# MCU152A_XDS110_MCU.net
KiCad netlist of a schematic drawn in Altium Designer
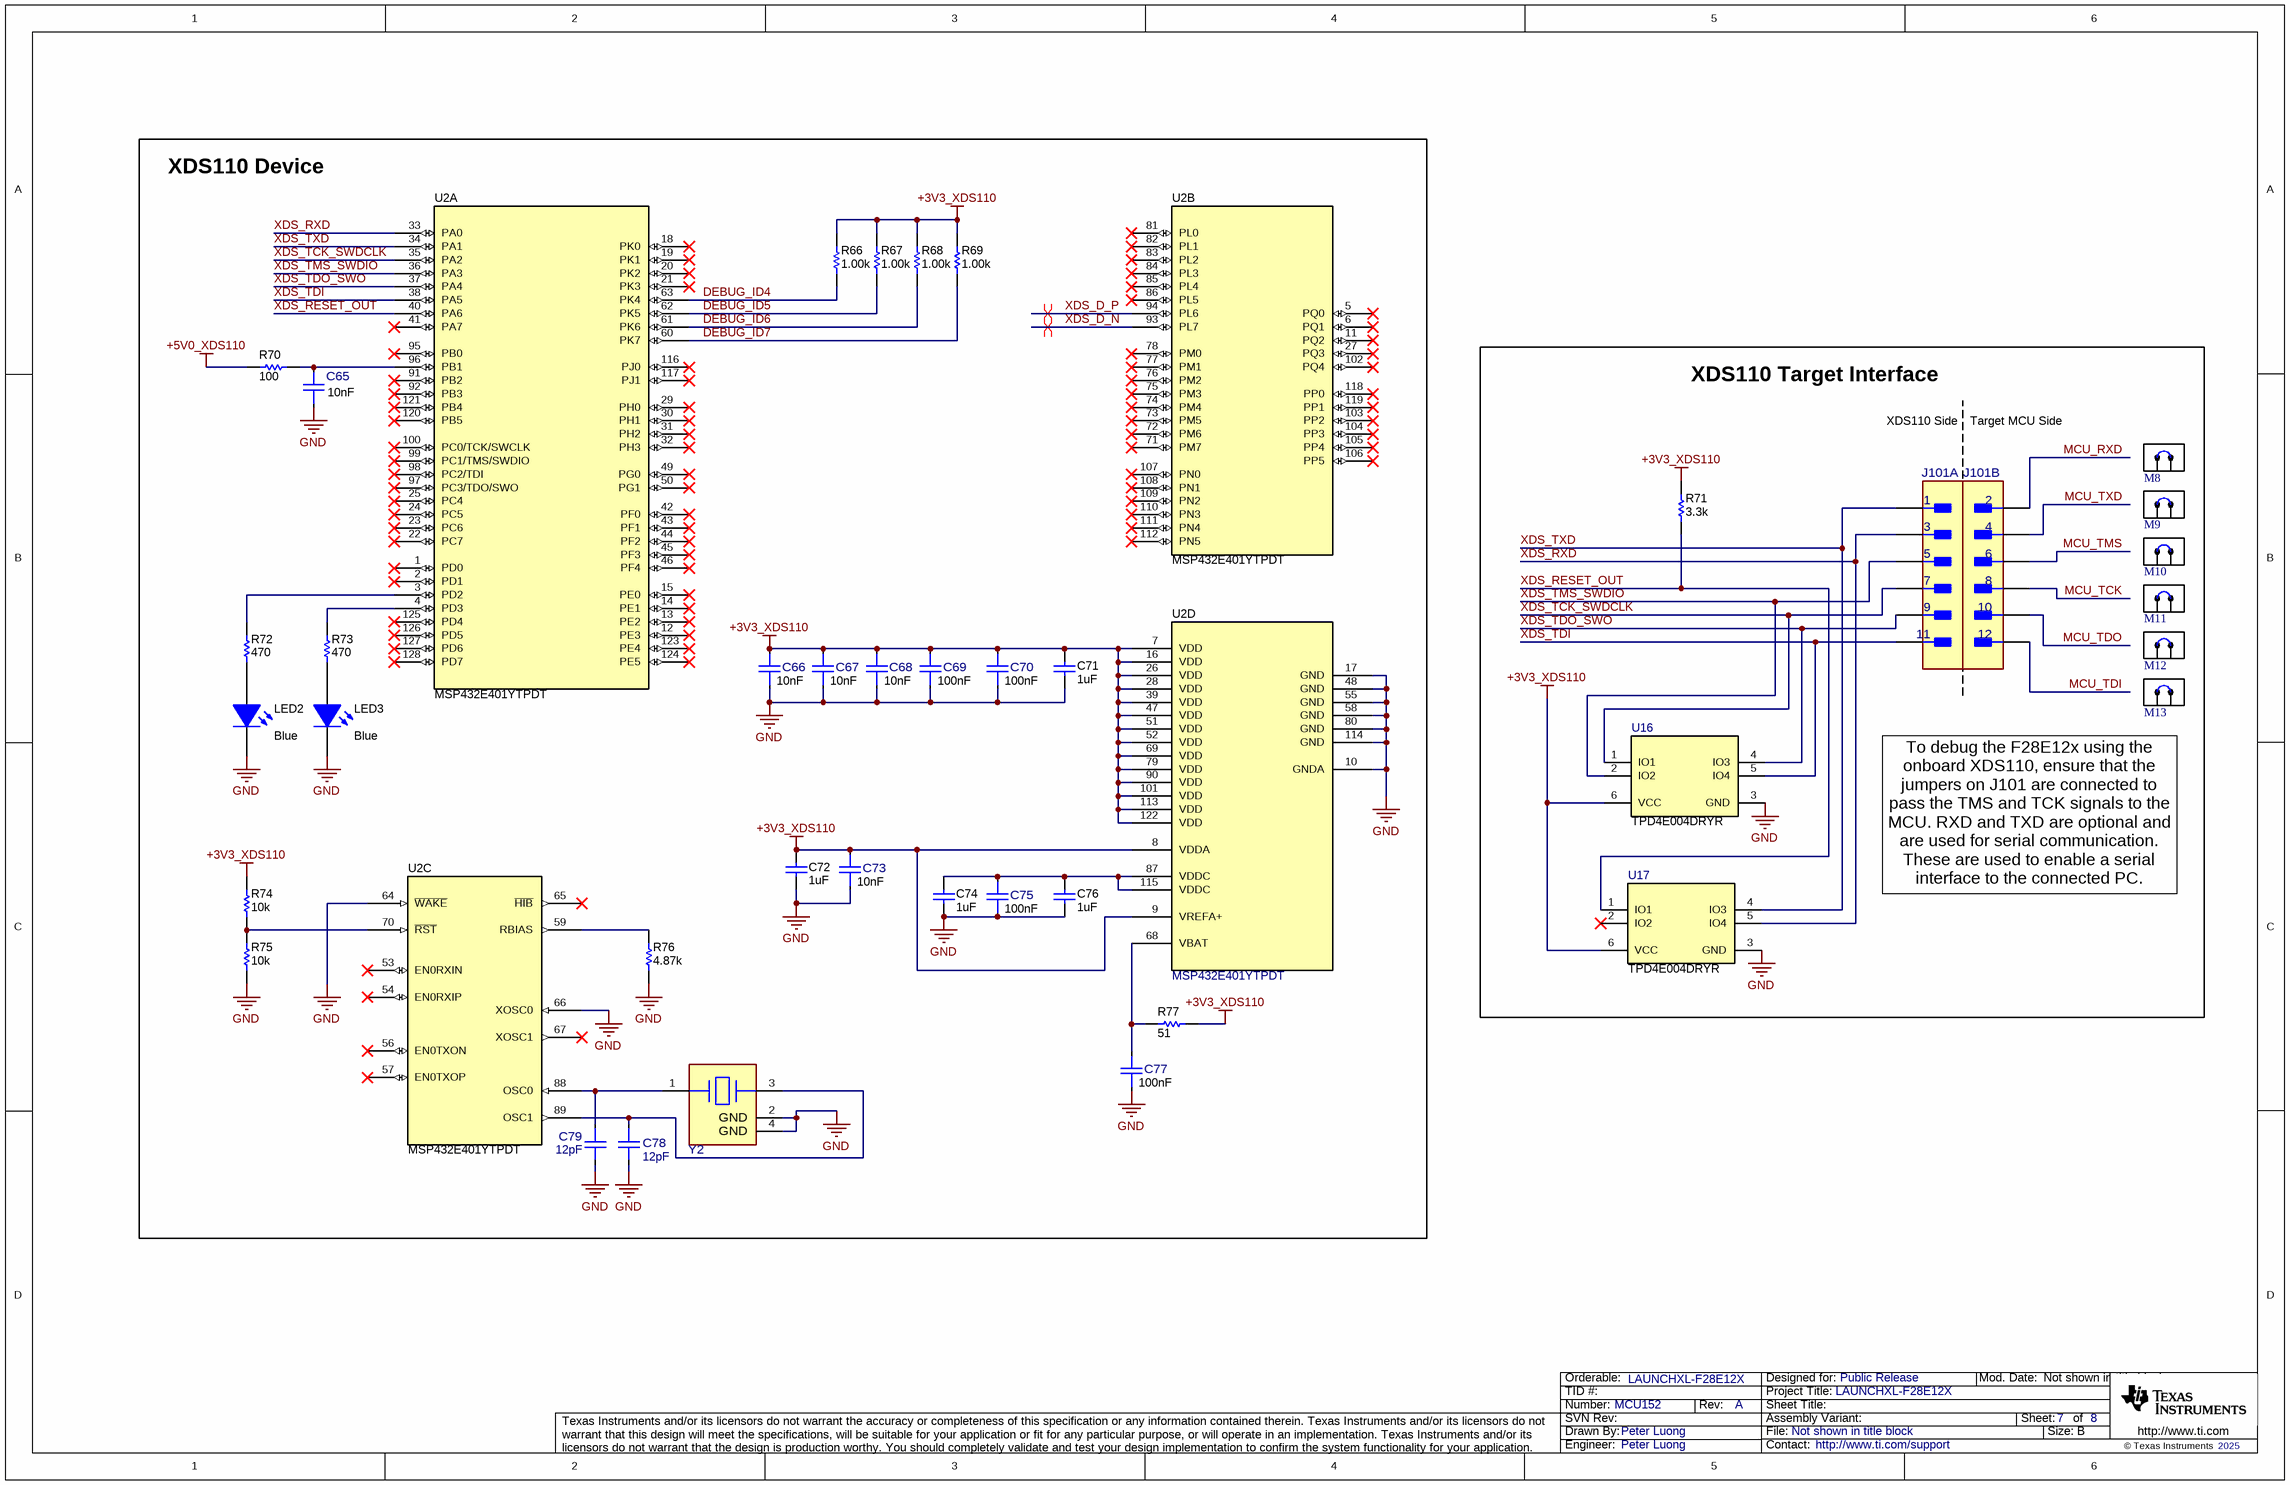
[diagram p0: MCU152A_XDS110_MCU.SchDoc]

(export (version "E")
  (design (tool "Eeschema 10.0.6"))
  (components
    (comp (ref "C65")
      (value "885012205050")
      (footprint "FP-885012205050_0402-MFG")
      (description "10000pF ±10% 25V Ceramic Capacitor X7R 0402 (1005 Metric)")
      (fields
        (field (name "MANUFACTURER") "Wurth Electronics")
        (field (name "CAP_F") "10nF")
        (field (name "MOUSER PART NUMBER") "710-885012205050")
      )
      (libsource (lib "Altium Vault - TI") (part "SYM-885012205050"))
    )
    (comp (ref "C66")
      (value "885012205050")
      (footprint "FP-885012205050_0402-MFG")
      (description "10000pF ±10% 25V Ceramic Capacitor X7R 0402 (1005 Metric)")
      (fields
        (field (name "MANUFACTURER") "Wurth Electronics")
        (field (name "CAP_F") "10nF")
        (field (name "MOUSER PART NUMBER") "710-885012205050")
      )
      (libsource (lib "Altium Vault - TI") (part "SYM-885012205050"))
    )
    (comp (ref "C67")
      (value "885012205050")
      (footprint "FP-885012205050_0402-MFG")
      (description "10000pF ±10% 25V Ceramic Capacitor X7R 0402 (1005 Metric)")
      (fields
        (field (name "MANUFACTURER") "Wurth Electronics")
        (field (name "CAP_F") "10nF")
        (field (name "MOUSER PART NUMBER") "710-885012205050")
      )
      (libsource (lib "Altium Vault - TI") (part "SYM-885012205050"))
    )
    (comp (ref "C68")
      (value "885012205050")
      (footprint "FP-885012205050_0402-MFG")
      (description "10000pF ±10% 25V Ceramic Capacitor X7R 0402 (1005 Metric)")
      (fields
        (field (name "MANUFACTURER") "Wurth Electronics")
        (field (name "CAP_F") "10nF")
        (field (name "MOUSER PART NUMBER") "710-885012205050")
      )
      (libsource (lib "Altium Vault - TI") (part "SYM-885012205050"))
    )
    (comp (ref "C69")
      (value "885012205018")
      (footprint "FP-885012205018_0402-MFG")
      (description "0.1µF ±10% 10V Ceramic Capacitor X7R 0402 (1005 Metric)")
      (fields
        (field (name "MANUFACTURER") "Wurth Electronics")
        (field (name "MOUSER PART NUMBER") "710-885012205018")
        (field (name "CAP_F") "100nF")
      )
      (libsource (lib "Altium Vault - TI") (part "SYM-885012205018"))
    )
    (comp (ref "C70")
      (value "885012205018")
      (footprint "FP-885012205018_0402-MFG")
      (description "0.1µF ±10% 10V Ceramic Capacitor X7R 0402 (1005 Metric)")
      (fields
        (field (name "MANUFACTURER") "Wurth Electronics")
        (field (name "MOUSER PART NUMBER") "710-885012205018")
        (field (name "CAP_F") "100nF")
      )
      (libsource (lib "Altium Vault - TI") (part "SYM-885012205018"))
    )
    (comp (ref "C71")
      (value "885012105012")
      (footprint "0402")
      (description "CAP, CERM, 1 uF, 10 V,+/- 20%, X5R, 0402")
      (fields
        (field (name "VALUEDISPLAYED") "1uF")
        (field (name "MANUFACTURER") "Wurth Elektronik")
        (field (name "PUBLISHER") "Texas Instruments")
      )
      (libsource (lib "Altium Vault - TI") (part "Capacitor"))
    )
    (comp (ref "C72")
      (value "885012105012")
      (footprint "0402")
      (description "CAP, CERM, 1 uF, 10 V,+/- 20%, X5R, 0402")
      (fields
        (field (name "VALUEDISPLAYED") "1uF")
        (field (name "MANUFACTURER") "Wurth Elektronik")
        (field (name "PUBLISHER") "Texas Instruments")
      )
      (libsource (lib "Altium Vault - TI") (part "Capacitor"))
    )
    (comp (ref "C73")
      (value "885012205050")
      (footprint "FP-885012205050_0402-MFG")
      (description "10000pF ±10% 25V Ceramic Capacitor X7R 0402 (1005 Metric)")
      (fields
        (field (name "MANUFACTURER") "Wurth Electronics")
        (field (name "CAP_F") "10nF")
        (field (name "MOUSER PART NUMBER") "710-885012205050")
      )
      (libsource (lib "Altium Vault - TI") (part "SYM-885012205050"))
    )
    (comp (ref "C74")
      (value "885012105012")
      (footprint "0402")
      (description "CAP, CERM, 1 uF, 10 V,+/- 20%, X5R, 0402")
      (fields
        (field (name "VALUEDISPLAYED") "1uF")
        (field (name "MANUFACTURER") "Wurth Elektronik")
        (field (name "PUBLISHER") "Texas Instruments")
      )
      (libsource (lib "Altium Vault - TI") (part "Capacitor"))
    )
    (comp (ref "C75")
      (value "885012205018")
      (footprint "FP-885012205018_0402-MFG")
      (description "0.1µF ±10% 10V Ceramic Capacitor X7R 0402 (1005 Metric)")
      (fields
        (field (name "MANUFACTURER") "Wurth Electronics")
        (field (name "MOUSER PART NUMBER") "710-885012205018")
        (field (name "CAP_F") "100nF")
      )
      (libsource (lib "Altium Vault - TI") (part "SYM-885012205018"))
    )
    (comp (ref "C76")
      (value "885012105012")
      (footprint "0402")
      (description "CAP, CERM, 1 uF, 10 V,+/- 20%, X5R, 0402")
      (fields
        (field (name "VALUEDISPLAYED") "1uF")
        (field (name "MANUFACTURER") "Wurth Elektronik")
        (field (name "PUBLISHER") "Texas Instruments")
      )
      (libsource (lib "Altium Vault - TI") (part "Capacitor"))
    )
    (comp (ref "C77")
      (value "885012205018")
      (footprint "FP-885012205018_0402-MFG")
      (description "0.1µF ±10% 10V Ceramic Capacitor X7R 0402 (1005 Metric)")
      (fields
        (field (name "MANUFACTURER") "Wurth Electronics")
        (field (name "MOUSER PART NUMBER") "710-885012205018")
        (field (name "CAP_F") "100nF")
      )
      (libsource (lib "Altium Vault - TI") (part "SYM-885012205018"))
    )
    (comp (ref "C78")
      (value "885392005127")
      (footprint "FP-885392005127_0402-MFG")
      (description "12 pF ±2% 50V Ceramic Capacitor C0G, NP0 0402 (1005 Metric)")
      (fields
        (field (name "MANUFACTURER") "Wurth")
        (field (name "VALUEDISPLAYED") "12pF")
        (field (name "DIGIKEY PART NUMBER") "732-885392005127CT-ND")
      )
      (libsource (lib "Altium Vault - TI") (part "SYM-885392005127"))
    )
    (comp (ref "C79")
      (value "885392005127")
      (footprint "FP-885392005127_0402-MFG")
      (description "12 pF ±2% 50V Ceramic Capacitor C0G, NP0 0402 (1005 Metric)")
      (fields
        (field (name "MANUFACTURER") "Wurth")
        (field (name "VALUEDISPLAYED") "12pF")
        (field (name "DIGIKEY PART NUMBER") "732-885392005127CT-ND")
      )
      (libsource (lib "Altium Vault - TI") (part "SYM-885392005127"))
    )
    (comp (ref "J101")
      (value "61301221121")
      (footprint "FP-61301221121_HDR12-MFG")
      (description "THT Vertical Pin Header WR-PHD, Pitch 2.54 mm, Dual Row, 12 pins")
      (fields
        (field (name "MOUSER PART NUMBER") "710-61301221121")
        (field (name "MANUFACTURER") "Wurth Electronics")
      )
      (libsource (lib "Altium Vault - TI") (part "SYM-61301221121"))
    )
    (comp (ref "LED2")
      (value "Blue")
      (footprint "WL-SMCW_Blue_0805")
      (description "LED, Blue, SMD")
      (fields (field (name "MANUFACTURER") "Wurth Elektronik") (field (name "PARTNUMBER") "150080BS75000"))
      (libsource (lib "Altium Vault - TI") (part "LED_A2_K1"))
    )
    (comp (ref "LED3")
      (value "Blue")
      (footprint "WL-SMCW_Blue_0805")
      (description "LED, Blue, SMD")
      (fields (field (name "MANUFACTURER") "Wurth Elektronik") (field (name "PARTNUMBER") "150080BS75000"))
      (libsource (lib "Altium Vault - TI") (part "LED_A2_K1"))
    )
    (comp (ref "M8")
      (value "60900213421")
      (footprint "Wurth_60900213421")
      (description "Shunt, 2.54mm, Gold, Black")
      (fields (field (name "MANUFACTURER") "Wurth Elektronik"))
      (libsource (lib "Altium Vault - TI") (part "Shunt"))
    )
    (comp (ref "M9")
      (value "60900213421")
      (footprint "Wurth_60900213421")
      (description "Shunt, 2.54mm, Gold, Black")
      (fields (field (name "MANUFACTURER") "Wurth Elektronik"))
      (libsource (lib "Altium Vault - TI") (part "Shunt"))
    )
    (comp (ref "M10")
      (value "60900213421")
      (footprint "Wurth_60900213421")
      (description "Shunt, 2.54mm, Gold, Black")
      (fields (field (name "MANUFACTURER") "Wurth Elektronik"))
      (libsource (lib "Altium Vault - TI") (part "Shunt"))
    )
    (comp (ref "M11")
      (value "60900213421")
      (footprint "Wurth_60900213421")
      (description "Shunt, 2.54mm, Gold, Black")
      (fields (field (name "MANUFACTURER") "Wurth Elektronik"))
      (libsource (lib "Altium Vault - TI") (part "Shunt"))
    )
    (comp (ref "M12")
      (value "60900213421")
      (footprint "Wurth_60900213421")
      (description "Shunt, 2.54mm, Gold, Black")
      (fields (field (name "MANUFACTURER") "Wurth Elektronik"))
      (libsource (lib "Altium Vault - TI") (part "Shunt"))
    )
    (comp (ref "M13")
      (value "60900213421")
      (footprint "Wurth_60900213421")
      (description "Shunt, 2.54mm, Gold, Black")
      (fields (field (name "MANUFACTURER") "Wurth Elektronik"))
      (libsource (lib "Altium Vault - TI") (part "Shunt"))
    )
    (comp (ref "R66")
      (value "CRCW04021K00FKED")
      (footprint "0402")
      (description "RES, 1.00 k, 1%, 0.063 W, AEC-Q200 Grade 0, 0402")
      (fields (field (name "MANUFACTURER") "Vishay-Dale") (field (name "VALUEDISPLAYED") "1.00k"))
      (libsource (lib "Altium Vault - TI") (part "Resistor"))
    )
    (comp (ref "R67")
      (value "CRCW04021K00FKED")
      (footprint "0402")
      (description "RES, 1.00 k, 1%, 0.063 W, AEC-Q200 Grade 0, 0402")
      (fields (field (name "MANUFACTURER") "Vishay-Dale") (field (name "VALUEDISPLAYED") "1.00k"))
      (libsource (lib "Altium Vault - TI") (part "Resistor"))
    )
    (comp (ref "R68")
      (value "CRCW04021K00FKED")
      (footprint "0402")
      (description "RES, 1.00 k, 1%, 0.063 W, AEC-Q200 Grade 0, 0402")
      (fields (field (name "MANUFACTURER") "Vishay-Dale") (field (name "VALUEDISPLAYED") "1.00k"))
      (libsource (lib "Altium Vault - TI") (part "Resistor"))
    )
    (comp (ref "R69")
      (value "CRCW04021K00FKED")
      (footprint "0402")
      (description "RES, 1.00 k, 1%, 0.063 W, AEC-Q200 Grade 0, 0402")
      (fields (field (name "MANUFACTURER") "Vishay-Dale") (field (name "VALUEDISPLAYED") "1.00k"))
      (libsource (lib "Altium Vault - TI") (part "Resistor"))
    )
    (comp (ref "R70")
      (value "CRCW0402100RJNED")
      (footprint "0402")
      (description "RES, 100, 5%, 0.063 W, AEC-Q200 Grade 0, 0402")
      (fields (field (name "VALUEDISPLAYED") "100") (field (name "MANUFACTURER") "Vishay-Dale"))
      (libsource (lib "Altium Vault - TI") (part "Resistor"))
    )
    (comp (ref "R71")
      (value "CRCW04023K30JNED")
      (footprint "0402")
      (description "RES, 3.3 k, 5%, 0.063 W, AEC-Q200 Grade 0, 0402")
      (fields (field (name "VALUEDISPLAYED") "3.3k") (field (name "MANUFACTURER") "Vishay-Dale"))
      (libsource (lib "Altium Vault - TI") (part "Resistor"))
    )
    (comp (ref "R72")
      (value "RC0402FR-07470RL")
      (footprint "0402")
      (description "RES, 470, 1%, 0.063 W, 0402")
      (fields
        (field (name "MANUFACTURER") "Yageo America")
        (field (name "VALUEDISPLAYED") "470")
        (field (name "PUBLISHER") "Texas Instruments")
      )
      (libsource (lib "Altium Vault - TI") (part "Resistor"))
    )
    (comp (ref "R73")
      (value "RC0402FR-07470RL")
      (footprint "0402")
      (description "RES, 470, 1%, 0.063 W, 0402")
      (fields
        (field (name "MANUFACTURER") "Yageo America")
        (field (name "VALUEDISPLAYED") "470")
        (field (name "PUBLISHER") "Texas Instruments")
      )
      (libsource (lib "Altium Vault - TI") (part "Resistor"))
    )
    (comp (ref "R74")
      (value "CRCW040210K0JNED")
      (footprint "0402")
      (description "RES, 10 k, 5%, 0.063 W, AEC-Q200 Grade 0, 0402")
      (fields (field (name "VALUEDISPLAYED") "10k") (field (name "MANUFACTURER") "Vishay-Dale"))
      (libsource (lib "Altium Vault - TI") (part "Resistor"))
    )
    (comp (ref "R75")
      (value "CRCW040210K0JNED")
      (footprint "0402")
      (description "RES, 10 k, 5%, 0.063 W, AEC-Q200 Grade 0, 0402")
      (fields (field (name "VALUEDISPLAYED") "10k") (field (name "MANUFACTURER") "Vishay-Dale"))
      (libsource (lib "Altium Vault - TI") (part "Resistor"))
    )
    (comp (ref "R76")
      (value "CRCW04024K87FKED")
      (footprint "0402")
      (description "RES, 4.87 k, 1%, 0.063 W, AEC-Q200 Grade 0, 0402")
      (fields (field (name "VALUEDISPLAYED") "4.87k") (field (name "MANUFACTURER") "Vishay-Dale"))
      (libsource (lib "Altium Vault - TI") (part "Resistor"))
    )
    (comp (ref "R77")
      (value "CRCW040251R0JNED")
      (footprint "0402")
      (description "RES, 51, 5%, 0.063 W, AEC-Q200 Grade 0, 0402")
      (fields (field (name "VALUEDISPLAYED") "51") (field (name "MANUFACTURER") "Vishay-Dale"))
      (libsource (lib "Altium Vault - TI") (part "Resistor"))
    )
    (comp (ref "U2")
      (value "MSP432E401YTPDT")
      (footprint "PDT0128A")
      (description "MSP432E401YTPDT, PDT0128A (TQFP-128)")
      (fields
        (field (name "ALTERNATE PARTNUMBER") "MSP432E401YTPDTR")
        (field (name "MANUFACTURER") "Texas Instruments")
        (field (name "PARTNUMBER") "MSP432E401YTPDT")
      )
      (libsource (lib "Altium Vault - TI") (part "MSP432E401YTPDT"))
    )
    (comp (ref "U16")
      (value "TPD4E004DRYR")
      (footprint "DRY0006A")
      (description "4-Channel ESD Protection Array for High-Speed Data Interfaces, DRY0006A (USON-6)")
      (fields (field (name "MANUFACTURER") "Texas Instruments") (field (name "PARTNUMBER") "TPD4E004DRYR"))
      (libsource (lib "Altium Vault - TI") (part "TI-TPD4E004-SON_DRY-6"))
    )
    (comp (ref "U17")
      (value "TPD4E004DRYR")
      (footprint "DRY0006A")
      (description "4-Channel ESD Protection Array for High-Speed Data Interfaces, DRY0006A (USON-6)")
      (fields (field (name "MANUFACTURER") "Texas Instruments") (field (name "PARTNUMBER") "TPD4E004DRYR"))
      (libsource (lib "Altium Vault - TI") (part "TI-TPD4E004-SON_DRY-6"))
    )
    (comp (ref "Y2")
      (value "830064296")
      (footprint "FP-830064296_SMT4_3MM4_2MM7-MFG")
      (description "Crystal 16 MHz ±20ppm Crystal 8pF 70 Ohms 4-SMD, No Lead")
      (fields
        (field (name "MOUSER PART NUMBER") "710-830064296")
        (field (name "DIGIKEY PART NUMBER") "732-830064296CT-ND")
      )
      (libsource (lib "Altium Vault - TI") (part "SYM-830064296"))
    )
  )
  (nets
    (net (code "1") (name "+3V3_XDS110") (class "Default")
      (node (ref "C66") (pin "2") (pinfunction "2_2") (pintype "passive"))
      (node (ref "C67") (pin "2") (pinfunction "2_2") (pintype "passive"))
      (node (ref "C68") (pin "2") (pinfunction "2_2") (pintype "passive"))
      (node (ref "C69") (pin "2") (pinfunction "2_2") (pintype "passive"))
      (node (ref "C70") (pin "2") (pinfunction "2_2") (pintype "passive"))
      (node (ref "C71") (pin "1") (pinfunction "1_1") (pintype "passive"))
      (node (ref "C72") (pin "1") (pinfunction "1_1") (pintype "passive"))
      (node (ref "C73") (pin "2") (pinfunction "2_2") (pintype "passive"))
      (node (ref "R66") (pin "2") (pinfunction "2_2") (pintype "passive"))
      (node (ref "R67") (pin "2") (pinfunction "2_2") (pintype "passive"))
      (node (ref "R68") (pin "2") (pinfunction "2_2") (pintype "passive"))
      (node (ref "R69") (pin "2") (pinfunction "2_2") (pintype "passive"))
      (node (ref "R71") (pin "2") (pinfunction "2_2") (pintype "passive"))
      (node (ref "R74") (pin "2") (pinfunction "2_2") (pintype "passive"))
      (node (ref "R77") (pin "2") (pinfunction "2_2") (pintype "passive"))
      (node (ref "U16") (pin "6") (pinfunction "VCC_6") (pintype "power_in"))
      (node (ref "U17") (pin "6") (pinfunction "VCC_6") (pintype "power_in"))
      (node (ref "U2") (pin "101") (pinfunction "VDD_101") (pintype "power_in"))
      (node (ref "U2") (pin "113") (pinfunction "VDD_113") (pintype "power_in"))
      (node (ref "U2") (pin "122") (pinfunction "VDD_122") (pintype "power_in"))
      (node (ref "U2") (pin "16") (pinfunction "VDD_16") (pintype "power_in"))
      (node (ref "U2") (pin "26") (pinfunction "VDD_26") (pintype "power_in"))
      (node (ref "U2") (pin "28") (pinfunction "VDD_28") (pintype "power_in"))
      (node (ref "U2") (pin "39") (pinfunction "VDD_39") (pintype "power_in"))
      (node (ref "U2") (pin "47") (pinfunction "VDD_47") (pintype "power_in"))
      (node (ref "U2") (pin "51") (pinfunction "VDD_51") (pintype "power_in"))
      (node (ref "U2") (pin "52") (pinfunction "VDD_52") (pintype "power_in"))
      (node (ref "U2") (pin "69") (pinfunction "VDD_69") (pintype "power_in"))
      (node (ref "U2") (pin "7") (pinfunction "VDD_7") (pintype "power_in"))
      (node (ref "U2") (pin "79") (pinfunction "VDD_79") (pintype "power_in"))
      (node (ref "U2") (pin "8") (pinfunction "VDDA_8") (pintype "power_in"))
      (node (ref "U2") (pin "9") (pinfunction "VREFA+_9") (pintype "power_in"))
      (node (ref "U2") (pin "90") (pinfunction "VDD_90") (pintype "power_in"))
    )
    (net (code "2") (name "+5V0_XDS110") (class "Default")
      (node (ref "R70") (pin "1") (pinfunction "1_1") (pintype "passive"))
    )
    (net (code "3") (name "/DEBUG_ID4") (class "Default")
      (node (ref "R66") (pin "1") (pinfunction "1_1") (pintype "passive"))
      (node (ref "U2") (pin "63") (pinfunction "PK4_63") (pintype "bidirectional"))
    )
    (net (code "4") (name "/DEBUG_ID5") (class "Default")
      (node (ref "R67") (pin "1") (pinfunction "1_1") (pintype "passive"))
      (node (ref "U2") (pin "62") (pinfunction "PK5_62") (pintype "bidirectional"))
    )
    (net (code "5") (name "/DEBUG_ID6") (class "Default")
      (node (ref "R68") (pin "1") (pinfunction "1_1") (pintype "passive"))
      (node (ref "U2") (pin "61") (pinfunction "PK6_61") (pintype "bidirectional"))
    )
    (net (code "6") (name "/DEBUG_ID7") (class "Default")
      (node (ref "R69") (pin "1") (pinfunction "1_1") (pintype "passive"))
      (node (ref "U2") (pin "60") (pinfunction "PK7_60") (pintype "bidirectional"))
    )
    (net (code "7") (name "/MCU_RXD") (class "Default")
      (node (ref "J101") (pin "2") (pinfunction "2_2") (pintype "passive"))
    )
    (net (code "8") (name "/MCU_TCK") (class "Default")
      (node (ref "J101") (pin "8") (pinfunction "8_8") (pintype "passive"))
    )
    (net (code "9") (name "/MCU_TDI") (class "Default")
      (node (ref "J101") (pin "12") (pinfunction "12_12") (pintype "passive"))
    )
    (net (code "10") (name "/MCU_TDO") (class "Default")
      (node (ref "J101") (pin "10") (pinfunction "10_10") (pintype "passive"))
    )
    (net (code "11") (name "/MCU_TMS") (class "Default")
      (node (ref "J101") (pin "6") (pinfunction "6_6") (pintype "passive"))
    )
    (net (code "12") (name "/MCU_TXD") (class "Default")
      (node (ref "J101") (pin "4") (pinfunction "4_4") (pintype "passive"))
    )
    (net (code "13") (name "/XDS_D_N") (class "Default")
      (node (ref "U2") (pin "93") (pinfunction "PL7_93") (pintype "bidirectional"))
    )
    (net (code "14") (name "/XDS_D_P") (class "Default")
      (node (ref "U2") (pin "94") (pinfunction "PL6_94") (pintype "bidirectional"))
    )
    (net (code "15") (name "/XDS_RESET_OUT") (class "Default")
      (node (ref "R71") (pin "1") (pinfunction "1_1") (pintype "passive"))
      (node (ref "U17") (pin "1") (pinfunction "IO1_1") (pintype "passive"))
      (node (ref "U2") (pin "40") (pinfunction "PA6_40") (pintype "bidirectional"))
    )
    (net (code "16") (name "/XDS_RXD") (class "Default")
      (node (ref "J101") (pin "3") (pinfunction "3_3") (pintype "passive"))
      (node (ref "U17") (pin "5") (pinfunction "IO4_5") (pintype "passive"))
      (node (ref "U2") (pin "33") (pinfunction "PA0_33") (pintype "bidirectional"))
    )
    (net (code "17") (name "/XDS_TCK_SWDCLK") (class "Default")
      (node (ref "J101") (pin "7") (pinfunction "7_7") (pintype "passive"))
      (node (ref "U16") (pin "1") (pinfunction "IO1_1") (pintype "passive"))
      (node (ref "U2") (pin "35") (pinfunction "PA2_35") (pintype "bidirectional"))
    )
    (net (code "18") (name "/XDS_TDI") (class "Default")
      (node (ref "J101") (pin "11") (pinfunction "11_11") (pintype "passive"))
      (node (ref "U16") (pin "5") (pinfunction "IO4_5") (pintype "passive"))
      (node (ref "U2") (pin "38") (pinfunction "PA5_38") (pintype "bidirectional"))
    )
    (net (code "19") (name "/XDS_TDO_SWO") (class "Default")
      (node (ref "J101") (pin "9") (pinfunction "9_9") (pintype "passive"))
      (node (ref "U16") (pin "4") (pinfunction "IO3_4") (pintype "passive"))
      (node (ref "U2") (pin "37") (pinfunction "PA4_37") (pintype "bidirectional"))
    )
    (net (code "20") (name "/XDS_TMS_SWDIO") (class "Default")
      (node (ref "J101") (pin "5") (pinfunction "5_5") (pintype "passive"))
      (node (ref "U16") (pin "2") (pinfunction "IO2_2") (pintype "passive"))
      (node (ref "U2") (pin "36") (pinfunction "PA3_36") (pintype "bidirectional"))
    )
    (net (code "21") (name "/XDS_TXD") (class "Default")
      (node (ref "J101") (pin "1") (pinfunction "1_1") (pintype "passive"))
      (node (ref "U17") (pin "4") (pinfunction "IO3_4") (pintype "passive"))
      (node (ref "U2") (pin "34") (pinfunction "PA1_34") (pintype "bidirectional"))
    )
    (net (code "22") (name "GND") (class "Default")
      (node (ref "C65") (pin "1") (pinfunction "1_1") (pintype "passive"))
      (node (ref "C66") (pin "1") (pinfunction "1_1") (pintype "passive"))
      (node (ref "C67") (pin "1") (pinfunction "1_1") (pintype "passive"))
      (node (ref "C68") (pin "1") (pinfunction "1_1") (pintype "passive"))
      (node (ref "C69") (pin "1") (pinfunction "1_1") (pintype "passive"))
      (node (ref "C70") (pin "1") (pinfunction "1_1") (pintype "passive"))
      (node (ref "C71") (pin "2") (pinfunction "2_2") (pintype "passive"))
      (node (ref "C72") (pin "2") (pinfunction "2_2") (pintype "passive"))
      (node (ref "C73") (pin "1") (pinfunction "1_1") (pintype "passive"))
      (node (ref "C74") (pin "2") (pinfunction "2_2") (pintype "passive"))
      (node (ref "C75") (pin "1") (pinfunction "1_1") (pintype "passive"))
      (node (ref "C76") (pin "2") (pinfunction "2_2") (pintype "passive"))
      (node (ref "C77") (pin "1") (pinfunction "1_1") (pintype "passive"))
      (node (ref "C78") (pin "2") (pinfunction "2_2") (pintype "passive"))
      (node (ref "C79") (pin "2") (pinfunction "2_2") (pintype "passive"))
      (node (ref "LED2") (pin "1") (pinfunction "K_1") (pintype "passive"))
      (node (ref "LED3") (pin "1") (pinfunction "K_1") (pintype "passive"))
      (node (ref "R75") (pin "1") (pinfunction "1_1") (pintype "passive"))
      (node (ref "R76") (pin "1") (pinfunction "1_1") (pintype "passive"))
      (node (ref "U16") (pin "3") (pinfunction "GND_3") (pintype "power_in"))
      (node (ref "U17") (pin "3") (pinfunction "GND_3") (pintype "power_in"))
      (node (ref "U2") (pin "10") (pinfunction "GNDA_10") (pintype "power_in"))
      (node (ref "U2") (pin "114") (pinfunction "GND_114") (pintype "power_in"))
      (node (ref "U2") (pin "17") (pinfunction "GND_17") (pintype "power_in"))
      (node (ref "U2") (pin "48") (pinfunction "GND_48") (pintype "power_in"))
      (node (ref "U2") (pin "55") (pinfunction "GND_55") (pintype "power_in"))
      (node (ref "U2") (pin "58") (pinfunction "GND_58") (pintype "power_in"))
      (node (ref "U2") (pin "64") (pinfunction "WAKE_64") (pintype "input"))
      (node (ref "U2") (pin "66") (pinfunction "XOSC0_66") (pintype "input"))
      (node (ref "U2") (pin "80") (pinfunction "GND_80") (pintype "power_in"))
      (node (ref "Y2") (pin "2") (pinfunction "GND_2") (pintype "power_in"))
      (node (ref "Y2") (pin "4") (pinfunction "GND_4") (pintype "power_in"))
    )
    (net (code "23") (name "Net-(C74-Pad1)") (class "Default")
      (node (ref "C74") (pin "1") (pinfunction "1_1") (pintype "passive"))
      (node (ref "C75") (pin "2") (pinfunction "2_2") (pintype "passive"))
      (node (ref "C76") (pin "1") (pinfunction "1_1") (pintype "passive"))
      (node (ref "U2") (pin "115") (pinfunction "VDDC_115") (pintype "power_in"))
      (node (ref "U2") (pin "87") (pinfunction "VDDC_87") (pintype "power_in"))
    )
    (net (code "24") (name "Net-(LED2-A)") (class "Default")
      (node (ref "LED2") (pin "2") (pinfunction "A_2") (pintype "passive"))
      (node (ref "R72") (pin "1") (pinfunction "1_1") (pintype "passive"))
    )
    (net (code "25") (name "Net-(LED3-A)") (class "Default")
      (node (ref "LED3") (pin "2") (pinfunction "A_2") (pintype "passive"))
      (node (ref "R73") (pin "1") (pinfunction "1_1") (pintype "passive"))
    )
    (net (code "26") (name "Net-(U2A-PB1)") (class "Default")
      (node (ref "C65") (pin "2") (pinfunction "2_2") (pintype "passive"))
      (node (ref "R70") (pin "2") (pinfunction "2_2") (pintype "passive"))
      (node (ref "U2") (pin "96") (pinfunction "PB1_96") (pintype "bidirectional"))
    )
    (net (code "27") (name "Net-(U2A-PD2)") (class "Default")
      (node (ref "R72") (pin "2") (pinfunction "2_2") (pintype "passive"))
      (node (ref "U2") (pin "3") (pinfunction "PD2_3") (pintype "bidirectional"))
    )
    (net (code "28") (name "Net-(U2A-PD3)") (class "Default")
      (node (ref "R73") (pin "2") (pinfunction "2_2") (pintype "passive"))
      (node (ref "U2") (pin "4") (pinfunction "PD3_4") (pintype "bidirectional"))
    )
    (net (code "29") (name "Net-(U2C-OSC0)") (class "Default")
      (node (ref "C79") (pin "1") (pinfunction "1_1") (pintype "passive"))
      (node (ref "U2") (pin "88") (pinfunction "OSC0_88") (pintype "input"))
      (node (ref "Y2") (pin "1") (pinfunction "1_Crystal_1") (pintype "passive"))
    )
    (net (code "30") (name "Net-(U2C-OSC1)") (class "Default")
      (node (ref "C78") (pin "1") (pinfunction "1_1") (pintype "passive"))
      (node (ref "U2") (pin "89") (pinfunction "OSC1_89") (pintype "output"))
      (node (ref "Y2") (pin "3") (pinfunction "2_Crystal_3") (pintype "passive"))
    )
    (net (code "31") (name "Net-(U2C-RBIAS)") (class "Default")
      (node (ref "R76") (pin "2") (pinfunction "2_2") (pintype "passive"))
      (node (ref "U2") (pin "59") (pinfunction "RBIAS_59") (pintype "output"))
    )
    (net (code "32") (name "Net-(U2C-RST)") (class "Default")
      (node (ref "R74") (pin "1") (pinfunction "1_1") (pintype "passive"))
      (node (ref "R75") (pin "2") (pinfunction "2_2") (pintype "passive"))
      (node (ref "U2") (pin "70") (pinfunction "RST_70") (pintype "input"))
    )
    (net (code "33") (name "Net-(U2D-VBAT)") (class "Default")
      (node (ref "C77") (pin "2") (pinfunction "2_2") (pintype "passive"))
      (node (ref "R77") (pin "1") (pinfunction "1_1") (pintype "passive"))
      (node (ref "U2") (pin "68") (pinfunction "VBAT_68") (pintype "power_in"))
    )
    (net (code "34") (name "unconnected-(U2A-PA7-Pad41)") (class "Default")
      (node (ref "U2") (pin "41") (pinfunction "PA7_41") (pintype "bidirectional+no_connect"))
    )
    (net (code "35") (name "unconnected-(U2A-PB0-Pad95)") (class "Default")
      (node (ref "U2") (pin "95") (pinfunction "PB0_95") (pintype "bidirectional+no_connect"))
    )
    (net (code "36") (name "unconnected-(U2A-PB2-Pad91)") (class "Default")
      (node (ref "U2") (pin "91") (pinfunction "PB2_91") (pintype "bidirectional+no_connect"))
    )
    (net (code "37") (name "unconnected-(U2A-PB3-Pad92)") (class "Default")
      (node (ref "U2") (pin "92") (pinfunction "PB3_92") (pintype "bidirectional+no_connect"))
    )
    (net (code "38") (name "unconnected-(U2A-PB4-Pad121)") (class "Default")
      (node (ref "U2") (pin "121") (pinfunction "PB4_121") (pintype "bidirectional+no_connect"))
    )
    (net (code "39") (name "unconnected-(U2A-PB5-Pad120)") (class "Default")
      (node (ref "U2") (pin "120") (pinfunction "PB5_120") (pintype "bidirectional+no_connect"))
    )
    (net (code "40") (name "unconnected-(U2A-PC0{slash}TCK{slash}SWCLK-Pad100)") (class "Default")
      (node (ref "U2") (pin "100") (pinfunction "PC0/TCK/SWCLK_100") (pintype "bidirectional+no_connect"))
    )
    (net (code "41") (name "unconnected-(U2A-PC1{slash}TMS{slash}SWDIO-Pad99)") (class "Default")
      (node (ref "U2") (pin "99") (pinfunction "PC1/TMS/SWDIO_99") (pintype "bidirectional+no_connect"))
    )
    (net (code "42") (name "unconnected-(U2A-PC2{slash}TDI-Pad98)") (class "Default")
      (node (ref "U2") (pin "98") (pinfunction "PC2/TDI_98") (pintype "bidirectional+no_connect"))
    )
    (net (code "43") (name "unconnected-(U2A-PC3{slash}TDO{slash}SWO-Pad97)") (class "Default")
      (node (ref "U2") (pin "97") (pinfunction "PC3/TDO/SWO_97") (pintype "bidirectional+no_connect"))
    )
    (net (code "44") (name "unconnected-(U2A-PC4-Pad25)") (class "Default")
      (node (ref "U2") (pin "25") (pinfunction "PC4_25") (pintype "bidirectional+no_connect"))
    )
    (net (code "45") (name "unconnected-(U2A-PC5-Pad24)") (class "Default")
      (node (ref "U2") (pin "24") (pinfunction "PC5_24") (pintype "bidirectional+no_connect"))
    )
    (net (code "46") (name "unconnected-(U2A-PC6-Pad23)") (class "Default")
      (node (ref "U2") (pin "23") (pinfunction "PC6_23") (pintype "bidirectional+no_connect"))
    )
    (net (code "47") (name "unconnected-(U2A-PC7-Pad22)") (class "Default")
      (node (ref "U2") (pin "22") (pinfunction "PC7_22") (pintype "bidirectional+no_connect"))
    )
    (net (code "48") (name "unconnected-(U2A-PD0-Pad1)") (class "Default")
      (node (ref "U2") (pin "1") (pinfunction "PD0_1") (pintype "bidirectional+no_connect"))
    )
    (net (code "49") (name "unconnected-(U2A-PD1-Pad2)") (class "Default")
      (node (ref "U2") (pin "2") (pinfunction "PD1_2") (pintype "bidirectional+no_connect"))
    )
    (net (code "50") (name "unconnected-(U2A-PD4-Pad125)") (class "Default")
      (node (ref "U2") (pin "125") (pinfunction "PD4_125") (pintype "bidirectional+no_connect"))
    )
    (net (code "51") (name "unconnected-(U2A-PD5-Pad126)") (class "Default")
      (node (ref "U2") (pin "126") (pinfunction "PD5_126") (pintype "bidirectional+no_connect"))
    )
    (net (code "52") (name "unconnected-(U2A-PD6-Pad127)") (class "Default")
      (node (ref "U2") (pin "127") (pinfunction "PD6_127") (pintype "bidirectional+no_connect"))
    )
    (net (code "53") (name "unconnected-(U2A-PD7-Pad128)") (class "Default")
      (node (ref "U2") (pin "128") (pinfunction "PD7_128") (pintype "bidirectional+no_connect"))
    )
    (net (code "54") (name "unconnected-(U2A-PE0-Pad15)") (class "Default")
      (node (ref "U2") (pin "15") (pinfunction "PE0_15") (pintype "bidirectional+no_connect"))
    )
    (net (code "55") (name "unconnected-(U2A-PE1-Pad14)") (class "Default")
      (node (ref "U2") (pin "14") (pinfunction "PE1_14") (pintype "bidirectional+no_connect"))
    )
    (net (code "56") (name "unconnected-(U2A-PE2-Pad13)") (class "Default")
      (node (ref "U2") (pin "13") (pinfunction "PE2_13") (pintype "bidirectional+no_connect"))
    )
    (net (code "57") (name "unconnected-(U2A-PE3-Pad12)") (class "Default")
      (node (ref "U2") (pin "12") (pinfunction "PE3_12") (pintype "bidirectional+no_connect"))
    )
    (net (code "58") (name "unconnected-(U2A-PE4-Pad123)") (class "Default")
      (node (ref "U2") (pin "123") (pinfunction "PE4_123") (pintype "bidirectional+no_connect"))
    )
    (net (code "59") (name "unconnected-(U2A-PE5-Pad124)") (class "Default")
      (node (ref "U2") (pin "124") (pinfunction "PE5_124") (pintype "bidirectional+no_connect"))
    )
    (net (code "60") (name "unconnected-(U2A-PF0-Pad42)") (class "Default")
      (node (ref "U2") (pin "42") (pinfunction "PF0_42") (pintype "bidirectional+no_connect"))
    )
    (net (code "61") (name "unconnected-(U2A-PF1-Pad43)") (class "Default")
      (node (ref "U2") (pin "43") (pinfunction "PF1_43") (pintype "bidirectional+no_connect"))
    )
    (net (code "62") (name "unconnected-(U2A-PF2-Pad44)") (class "Default")
      (node (ref "U2") (pin "44") (pinfunction "PF2_44") (pintype "bidirectional+no_connect"))
    )
    (net (code "63") (name "unconnected-(U2A-PF3-Pad45)") (class "Default")
      (node (ref "U2") (pin "45") (pinfunction "PF3_45") (pintype "bidirectional+no_connect"))
    )
    (net (code "64") (name "unconnected-(U2A-PF4-Pad46)") (class "Default")
      (node (ref "U2") (pin "46") (pinfunction "PF4_46") (pintype "bidirectional+no_connect"))
    )
    (net (code "65") (name "unconnected-(U2A-PG0-Pad49)") (class "Default")
      (node (ref "U2") (pin "49") (pinfunction "PG0_49") (pintype "bidirectional+no_connect"))
    )
    (net (code "66") (name "unconnected-(U2A-PG1-Pad50)") (class "Default")
      (node (ref "U2") (pin "50") (pinfunction "PG1_50") (pintype "bidirectional+no_connect"))
    )
    (net (code "67") (name "unconnected-(U2A-PH0-Pad29)") (class "Default")
      (node (ref "U2") (pin "29") (pinfunction "PH0_29") (pintype "bidirectional+no_connect"))
    )
    (net (code "68") (name "unconnected-(U2A-PH1-Pad30)") (class "Default")
      (node (ref "U2") (pin "30") (pinfunction "PH1_30") (pintype "bidirectional+no_connect"))
    )
    (net (code "69") (name "unconnected-(U2A-PH2-Pad31)") (class "Default")
      (node (ref "U2") (pin "31") (pinfunction "PH2_31") (pintype "bidirectional+no_connect"))
    )
    (net (code "70") (name "unconnected-(U2A-PH3-Pad32)") (class "Default")
      (node (ref "U2") (pin "32") (pinfunction "PH3_32") (pintype "bidirectional+no_connect"))
    )
    (net (code "71") (name "unconnected-(U2A-PJ0-Pad116)") (class "Default")
      (node (ref "U2") (pin "116") (pinfunction "PJ0_116") (pintype "bidirectional+no_connect"))
    )
    (net (code "72") (name "unconnected-(U2A-PJ1-Pad117)") (class "Default")
      (node (ref "U2") (pin "117") (pinfunction "PJ1_117") (pintype "bidirectional+no_connect"))
    )
    (net (code "73") (name "unconnected-(U2A-PK0-Pad18)") (class "Default")
      (node (ref "U2") (pin "18") (pinfunction "PK0_18") (pintype "bidirectional+no_connect"))
    )
    (net (code "74") (name "unconnected-(U2A-PK1-Pad19)") (class "Default")
      (node (ref "U2") (pin "19") (pinfunction "PK1_19") (pintype "bidirectional+no_connect"))
    )
    (net (code "75") (name "unconnected-(U2A-PK2-Pad20)") (class "Default")
      (node (ref "U2") (pin "20") (pinfunction "PK2_20") (pintype "bidirectional+no_connect"))
    )
    (net (code "76") (name "unconnected-(U2A-PK3-Pad21)") (class "Default")
      (node (ref "U2") (pin "21") (pinfunction "PK3_21") (pintype "bidirectional+no_connect"))
    )
    (net (code "77") (name "unconnected-(U2B-PL0-Pad81)") (class "Default")
      (node (ref "U2") (pin "81") (pinfunction "PL0_81") (pintype "bidirectional+no_connect"))
    )
    (net (code "78") (name "unconnected-(U2B-PL1-Pad82)") (class "Default")
      (node (ref "U2") (pin "82") (pinfunction "PL1_82") (pintype "bidirectional+no_connect"))
    )
    (net (code "79") (name "unconnected-(U2B-PL2-Pad83)") (class "Default")
      (node (ref "U2") (pin "83") (pinfunction "PL2_83") (pintype "bidirectional+no_connect"))
    )
    (net (code "80") (name "unconnected-(U2B-PL3-Pad84)") (class "Default")
      (node (ref "U2") (pin "84") (pinfunction "PL3_84") (pintype "bidirectional+no_connect"))
    )
    (net (code "81") (name "unconnected-(U2B-PL4-Pad85)") (class "Default")
      (node (ref "U2") (pin "85") (pinfunction "PL4_85") (pintype "bidirectional+no_connect"))
    )
    (net (code "82") (name "unconnected-(U2B-PL5-Pad86)") (class "Default")
      (node (ref "U2") (pin "86") (pinfunction "PL5_86") (pintype "bidirectional+no_connect"))
    )
    (net (code "83") (name "unconnected-(U2B-PM0-Pad78)") (class "Default")
      (node (ref "U2") (pin "78") (pinfunction "PM0_78") (pintype "bidirectional+no_connect"))
    )
    (net (code "84") (name "unconnected-(U2B-PM1-Pad77)") (class "Default")
      (node (ref "U2") (pin "77") (pinfunction "PM1_77") (pintype "bidirectional+no_connect"))
    )
    (net (code "85") (name "unconnected-(U2B-PM2-Pad76)") (class "Default")
      (node (ref "U2") (pin "76") (pinfunction "PM2_76") (pintype "bidirectional+no_connect"))
    )
    (net (code "86") (name "unconnected-(U2B-PM3-Pad75)") (class "Default")
      (node (ref "U2") (pin "75") (pinfunction "PM3_75") (pintype "bidirectional+no_connect"))
    )
    (net (code "87") (name "unconnected-(U2B-PM4-Pad74)") (class "Default")
      (node (ref "U2") (pin "74") (pinfunction "PM4_74") (pintype "bidirectional+no_connect"))
    )
    (net (code "88") (name "unconnected-(U2B-PM5-Pad73)") (class "Default")
      (node (ref "U2") (pin "73") (pinfunction "PM5_73") (pintype "bidirectional+no_connect"))
    )
    (net (code "89") (name "unconnected-(U2B-PM6-Pad72)") (class "Default")
      (node (ref "U2") (pin "72") (pinfunction "PM6_72") (pintype "bidirectional+no_connect"))
    )
    (net (code "90") (name "unconnected-(U2B-PM7-Pad71)") (class "Default")
      (node (ref "U2") (pin "71") (pinfunction "PM7_71") (pintype "bidirectional+no_connect"))
    )
    (net (code "91") (name "unconnected-(U2B-PN0-Pad107)") (class "Default")
      (node (ref "U2") (pin "107") (pinfunction "PN0_107") (pintype "bidirectional+no_connect"))
    )
    (net (code "92") (name "unconnected-(U2B-PN1-Pad108)") (class "Default")
      (node (ref "U2") (pin "108") (pinfunction "PN1_108") (pintype "bidirectional+no_connect"))
    )
    (net (code "93") (name "unconnected-(U2B-PN2-Pad109)") (class "Default")
      (node (ref "U2") (pin "109") (pinfunction "PN2_109") (pintype "bidirectional+no_connect"))
    )
    (net (code "94") (name "unconnected-(U2B-PN3-Pad110)") (class "Default")
      (node (ref "U2") (pin "110") (pinfunction "PN3_110") (pintype "bidirectional+no_connect"))
    )
    (net (code "95") (name "unconnected-(U2B-PN4-Pad111)") (class "Default")
      (node (ref "U2") (pin "111") (pinfunction "PN4_111") (pintype "bidirectional+no_connect"))
    )
    (net (code "96") (name "unconnected-(U2B-PN5-Pad112)") (class "Default")
      (node (ref "U2") (pin "112") (pinfunction "PN5_112") (pintype "bidirectional+no_connect"))
    )
    (net (code "97") (name "unconnected-(U2B-PP0-Pad118)") (class "Default")
      (node (ref "U2") (pin "118") (pinfunction "PP0_118") (pintype "bidirectional+no_connect"))
    )
    (net (code "98") (name "unconnected-(U2B-PP1-Pad119)") (class "Default")
      (node (ref "U2") (pin "119") (pinfunction "PP1_119") (pintype "bidirectional+no_connect"))
    )
    (net (code "99") (name "unconnected-(U2B-PP2-Pad103)") (class "Default")
      (node (ref "U2") (pin "103") (pinfunction "PP2_103") (pintype "bidirectional+no_connect"))
    )
    (net (code "100") (name "unconnected-(U2B-PP3-Pad104)") (class "Default")
      (node (ref "U2") (pin "104") (pinfunction "PP3_104") (pintype "bidirectional+no_connect"))
    )
    (net (code "101") (name "unconnected-(U2B-PP4-Pad105)") (class "Default")
      (node (ref "U2") (pin "105") (pinfunction "PP4_105") (pintype "bidirectional+no_connect"))
    )
    (net (code "102") (name "unconnected-(U2B-PP5-Pad106)") (class "Default")
      (node (ref "U2") (pin "106") (pinfunction "PP5_106") (pintype "bidirectional+no_connect"))
    )
    (net (code "103") (name "unconnected-(U2B-PQ0-Pad5)") (class "Default")
      (node (ref "U2") (pin "5") (pinfunction "PQ0_5") (pintype "bidirectional+no_connect"))
    )
    (net (code "104") (name "unconnected-(U2B-PQ1-Pad6)") (class "Default")
      (node (ref "U2") (pin "6") (pinfunction "PQ1_6") (pintype "bidirectional+no_connect"))
    )
    (net (code "105") (name "unconnected-(U2B-PQ2-Pad11)") (class "Default")
      (node (ref "U2") (pin "11") (pinfunction "PQ2_11") (pintype "bidirectional+no_connect"))
    )
    (net (code "106") (name "unconnected-(U2B-PQ3-Pad27)") (class "Default")
      (node (ref "U2") (pin "27") (pinfunction "PQ3_27") (pintype "bidirectional+no_connect"))
    )
    (net (code "107") (name "unconnected-(U2B-PQ4-Pad102)") (class "Default")
      (node (ref "U2") (pin "102") (pinfunction "PQ4_102") (pintype "bidirectional+no_connect"))
    )
    (net (code "108") (name "unconnected-(U2C-EN0RXIN-Pad53)") (class "Default")
      (node (ref "U2") (pin "53") (pinfunction "EN0RXIN_53") (pintype "bidirectional+no_connect"))
    )
    (net (code "109") (name "unconnected-(U2C-EN0RXIP-Pad54)") (class "Default")
      (node (ref "U2") (pin "54") (pinfunction "EN0RXIP_54") (pintype "bidirectional+no_connect"))
    )
    (net (code "110") (name "unconnected-(U2C-EN0TXON-Pad56)") (class "Default")
      (node (ref "U2") (pin "56") (pinfunction "EN0TXON_56") (pintype "bidirectional+no_connect"))
    )
    (net (code "111") (name "unconnected-(U2C-EN0TXOP-Pad57)") (class "Default")
      (node (ref "U2") (pin "57") (pinfunction "EN0TXOP_57") (pintype "bidirectional+no_connect"))
    )
    (net (code "112") (name "unconnected-(U2C-HIB-Pad65)") (class "Default")
      (node (ref "U2") (pin "65") (pinfunction "HIB_65") (pintype "output+no_connect"))
    )
    (net (code "113") (name "unconnected-(U2C-XOSC1-Pad67)") (class "Default")
      (node (ref "U2") (pin "67") (pinfunction "XOSC1_67") (pintype "output+no_connect"))
    )
    (net (code "114") (name "unconnected-(U17-IO2-Pad2)") (class "Default")
      (node (ref "U17") (pin "2") (pinfunction "IO2_2") (pintype "passive+no_connect"))
    )
  )
)
